# rev_B.net
KiCad netlist of a schematic drawn in EAGLE
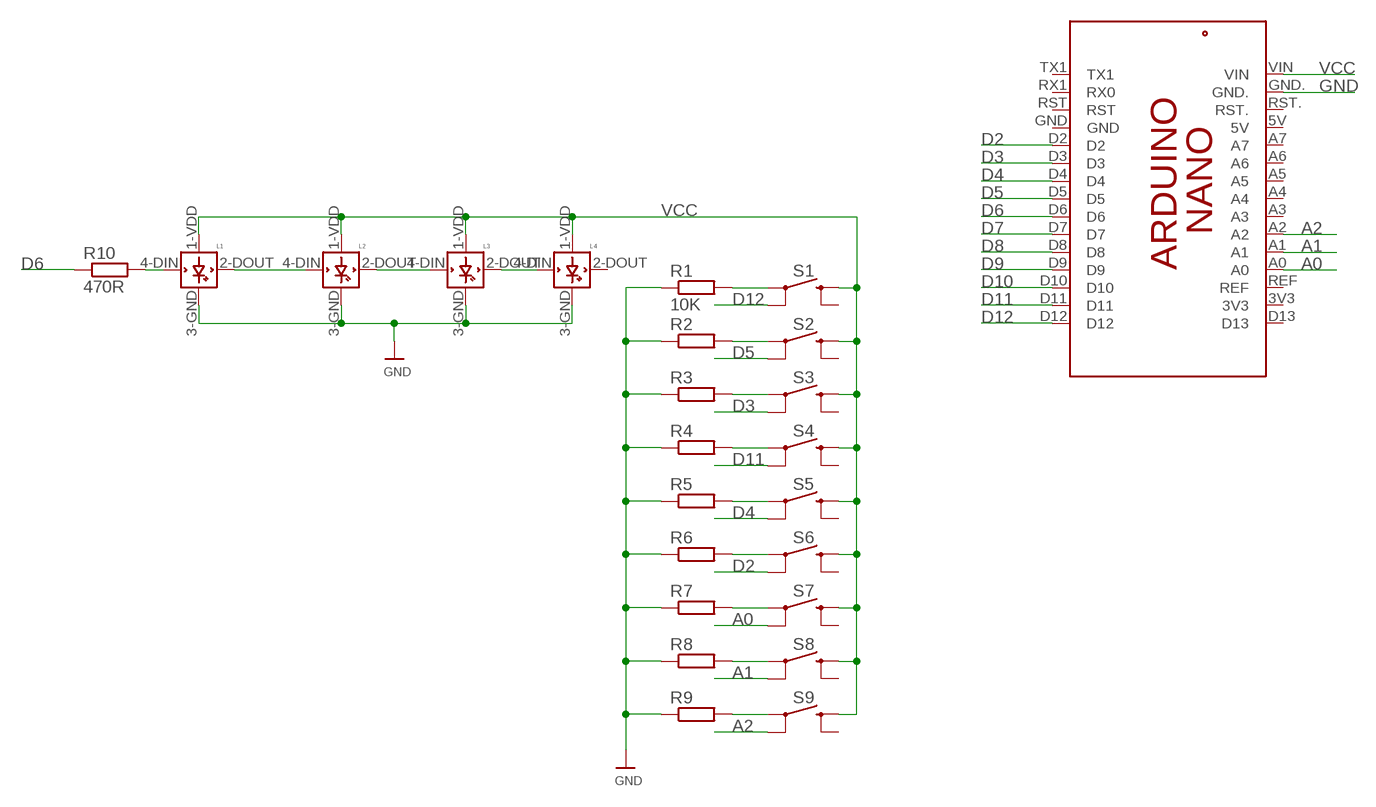
[diagram p0: schematic, sheet 1]

(export (version "E")
  (design (tool "Eeschema 10.0.6"))
  (components
    (comp (ref "L1")
      (value "WS2812B")
      (footprint "eagle-import:WS2812B")
      (libsource (lib "eagle-import") (part "WS2812B"))
    )
    (comp (ref "L2")
      (value "WS2812B")
      (footprint "eagle-import:WS2812B")
      (libsource (lib "eagle-import") (part "WS2812B"))
    )
    (comp (ref "L3")
      (value "WS2812B")
      (footprint "eagle-import:WS2812B")
      (libsource (lib "eagle-import") (part "WS2812B"))
    )
    (comp (ref "L4")
      (value "WS2812B")
      (footprint "eagle-import:WS2812B")
      (libsource (lib "eagle-import") (part "WS2812B"))
    )
    (comp (ref "PCB1")
      (value "ARDUINO_NANO")
      (footprint "eagle-import:ARDUINO_NANO")
      (libsource (lib "eagle-import") (part "ARDUINO_NANO"))
    )
    (comp (ref "R1")
      (value "10K")
      (footprint "eagle-import:R0805")
      (libsource (lib "eagle-import") (part "R-EU_R0805"))
    )
    (comp (ref "R2")
      (value "R-EU_R0805")
      (footprint "eagle-import:R0805")
      (libsource (lib "eagle-import") (part "R-EU_R0805"))
    )
    (comp (ref "R3")
      (value "R-EU_R0805")
      (footprint "eagle-import:R0805")
      (libsource (lib "eagle-import") (part "R-EU_R0805"))
    )
    (comp (ref "R4")
      (value "R-EU_R0805")
      (footprint "eagle-import:R0805")
      (libsource (lib "eagle-import") (part "R-EU_R0805"))
    )
    (comp (ref "R5")
      (value "R-EU_R0805")
      (footprint "eagle-import:R0805")
      (libsource (lib "eagle-import") (part "R-EU_R0805"))
    )
    (comp (ref "R6")
      (value "R-EU_R0805")
      (footprint "eagle-import:R0805")
      (libsource (lib "eagle-import") (part "R-EU_R0805"))
    )
    (comp (ref "R7")
      (value "R-EU_R0805")
      (footprint "eagle-import:R0805")
      (libsource (lib "eagle-import") (part "R-EU_R0805"))
    )
    (comp (ref "R8")
      (value "R-EU_R0805")
      (footprint "eagle-import:R0805")
      (libsource (lib "eagle-import") (part "R-EU_R0805"))
    )
    (comp (ref "R9")
      (value "R-EU_R0805")
      (footprint "eagle-import:R0805")
      (libsource (lib "eagle-import") (part "R-EU_R0805"))
    )
    (comp (ref "R10")
      (value "470R")
      (footprint "eagle-import:R0805")
      (libsource (lib "eagle-import") (part "R-EU_R0805"))
    )
    (comp (ref "S1")
      (value "TACT_SWITCH_12MM")
      (footprint "eagle-import:TACT_SWITCH_12MM")
      (libsource (lib "eagle-import") (part "TACT_SWITCH_12MM"))
    )
    (comp (ref "S2")
      (value "TACT_SWITCH_12MM")
      (footprint "eagle-import:TACT_SWITCH_12MM")
      (libsource (lib "eagle-import") (part "TACT_SWITCH_12MM"))
    )
    (comp (ref "S3")
      (value "TACT_SWITCH_12MM")
      (footprint "eagle-import:TACT_SWITCH_12MM")
      (libsource (lib "eagle-import") (part "TACT_SWITCH_12MM"))
    )
    (comp (ref "S4")
      (value "TACT_SWITCH_12MM")
      (footprint "eagle-import:TACT_SWITCH_12MM")
      (libsource (lib "eagle-import") (part "TACT_SWITCH_12MM"))
    )
    (comp (ref "S5")
      (value "TACT_SWITCH_12MM")
      (footprint "eagle-import:TACT_SWITCH_12MM")
      (libsource (lib "eagle-import") (part "TACT_SWITCH_12MM"))
    )
    (comp (ref "S6")
      (value "TACT_SWITCH_12MM")
      (footprint "eagle-import:TACT_SWITCH_12MM")
      (libsource (lib "eagle-import") (part "TACT_SWITCH_12MM"))
    )
    (comp (ref "S7")
      (value "TACT_SWITCH_12MM")
      (footprint "eagle-import:TACT_SWITCH_12MM")
      (libsource (lib "eagle-import") (part "TACT_SWITCH_12MM"))
    )
    (comp (ref "S8")
      (value "TACT_SWITCH_12MM")
      (footprint "eagle-import:TACT_SWITCH_12MM")
      (libsource (lib "eagle-import") (part "TACT_SWITCH_12MM"))
    )
    (comp (ref "S9")
      (value "TACT_SWITCH_12MM")
      (footprint "eagle-import:TACT_SWITCH_12MM")
      (libsource (lib "eagle-import") (part "TACT_SWITCH_12MM"))
    )
  )
  (nets
    (net (code "1") (name "/A0") (class "Default")
      (node (ref "PCB1") (pin "A0") (pinfunction "A0_A0") (pintype "bidirectional"))
      (node (ref "S7") (pin "2") (pinfunction "3_2") (pintype "passive"))
    )
    (net (code "2") (name "/A1") (class "Default")
      (node (ref "PCB1") (pin "A1") (pinfunction "A1_A1") (pintype "bidirectional"))
      (node (ref "S8") (pin "2") (pinfunction "3_2") (pintype "passive"))
    )
    (net (code "3") (name "/A2") (class "Default")
      (node (ref "PCB1") (pin "A2") (pinfunction "A2_A2") (pintype "bidirectional"))
      (node (ref "S9") (pin "2") (pinfunction "3_2") (pintype "passive"))
    )
    (net (code "4") (name "/D2") (class "Default")
      (node (ref "PCB1") (pin "D2") (pinfunction "D2_D2") (pintype "bidirectional"))
      (node (ref "S6") (pin "2") (pinfunction "3_2") (pintype "passive"))
    )
    (net (code "5") (name "/D3") (class "Default")
      (node (ref "PCB1") (pin "D3") (pinfunction "D3_D3") (pintype "bidirectional"))
      (node (ref "S3") (pin "2") (pinfunction "3_2") (pintype "passive"))
    )
    (net (code "6") (name "/D4") (class "Default")
      (node (ref "PCB1") (pin "D4") (pinfunction "D4_D4") (pintype "bidirectional"))
      (node (ref "S5") (pin "2") (pinfunction "3_2") (pintype "passive"))
    )
    (net (code "7") (name "/D5") (class "Default")
      (node (ref "PCB1") (pin "D5") (pinfunction "D5_D5") (pintype "bidirectional"))
      (node (ref "S2") (pin "2") (pinfunction "3_2") (pintype "passive"))
    )
    (net (code "8") (name "/D6") (class "Default")
      (node (ref "PCB1") (pin "D6") (pinfunction "D6_D6") (pintype "bidirectional"))
      (node (ref "R10") (pin "1") (pinfunction "1_1") (pintype "passive"))
    )
    (net (code "9") (name "/D7") (class "Default")
      (node (ref "PCB1") (pin "D7") (pinfunction "D7_D7") (pintype "bidirectional"))
    )
    (net (code "10") (name "/D8") (class "Default")
      (node (ref "PCB1") (pin "D8") (pinfunction "D8_D8") (pintype "bidirectional"))
    )
    (net (code "11") (name "/D9") (class "Default")
      (node (ref "PCB1") (pin "D9") (pinfunction "D9_D9") (pintype "bidirectional"))
    )
    (net (code "12") (name "/D10") (class "Default")
      (node (ref "PCB1") (pin "D10") (pinfunction "D10_D10") (pintype "bidirectional"))
    )
    (net (code "13") (name "/D11") (class "Default")
      (node (ref "PCB1") (pin "D11") (pinfunction "D11_D11") (pintype "bidirectional"))
      (node (ref "S4") (pin "2") (pinfunction "3_2") (pintype "passive"))
    )
    (net (code "14") (name "/D12") (class "Default")
      (node (ref "PCB1") (pin "D12") (pinfunction "D12_D12") (pintype "bidirectional"))
      (node (ref "S1") (pin "2") (pinfunction "3_2") (pintype "passive"))
    )
    (net (code "15") (name "/VCC") (class "Default")
      (node (ref "L1") (pin "1-VDD") (pinfunction "VDD_1-VDD") (pintype "bidirectional"))
      (node (ref "L2") (pin "1-VDD") (pinfunction "VDD_1-VDD") (pintype "bidirectional"))
      (node (ref "L3") (pin "1-VDD") (pinfunction "VDD_1-VDD") (pintype "bidirectional"))
      (node (ref "L4") (pin "1-VDD") (pinfunction "VDD_1-VDD") (pintype "bidirectional"))
      (node (ref "PCB1") (pin "VIN") (pinfunction "VIN_VIN") (pintype "bidirectional"))
      (node (ref "S1") (pin "3") (pinfunction "2_3") (pintype "passive"))
      (node (ref "S2") (pin "3") (pinfunction "2_3") (pintype "passive"))
      (node (ref "S3") (pin "3") (pinfunction "2_3") (pintype "passive"))
      (node (ref "S4") (pin "3") (pinfunction "2_3") (pintype "passive"))
      (node (ref "S5") (pin "3") (pinfunction "2_3") (pintype "passive"))
      (node (ref "S6") (pin "3") (pinfunction "2_3") (pintype "passive"))
      (node (ref "S7") (pin "3") (pinfunction "2_3") (pintype "passive"))
      (node (ref "S8") (pin "3") (pinfunction "2_3") (pintype "passive"))
      (node (ref "S9") (pin "3") (pinfunction "2_3") (pintype "passive"))
    )
    (net (code "16") (name "GND") (class "Default")
      (node (ref "L1") (pin "3-GND") (pinfunction "GND_3-GND") (pintype "bidirectional"))
      (node (ref "L2") (pin "3-GND") (pinfunction "GND_3-GND") (pintype "bidirectional"))
      (node (ref "L3") (pin "3-GND") (pinfunction "GND_3-GND") (pintype "bidirectional"))
      (node (ref "L4") (pin "3-GND") (pinfunction "GND_3-GND") (pintype "bidirectional"))
      (node (ref "PCB1") (pin "GND.") (pinfunction "GND._GND.") (pintype "bidirectional"))
      (node (ref "R1") (pin "1") (pinfunction "1_1") (pintype "passive"))
      (node (ref "R2") (pin "1") (pinfunction "1_1") (pintype "passive"))
      (node (ref "R3") (pin "1") (pinfunction "1_1") (pintype "passive"))
      (node (ref "R4") (pin "1") (pinfunction "1_1") (pintype "passive"))
      (node (ref "R5") (pin "1") (pinfunction "1_1") (pintype "passive"))
      (node (ref "R6") (pin "1") (pinfunction "1_1") (pintype "passive"))
      (node (ref "R7") (pin "1") (pinfunction "1_1") (pintype "passive"))
      (node (ref "R8") (pin "1") (pinfunction "1_1") (pintype "passive"))
      (node (ref "R9") (pin "1") (pinfunction "1_1") (pintype "passive"))
    )
    (net (code "17") (name "Net-(L1-DIN)") (class "Default")
      (node (ref "L1") (pin "4-DIN") (pinfunction "DIN_4-DIN") (pintype "input"))
      (node (ref "R10") (pin "2") (pinfunction "2_2") (pintype "passive"))
    )
    (net (code "18") (name "Net-(L1-DOUT)") (class "Default")
      (node (ref "L1") (pin "2-DOUT") (pinfunction "DOUT_2-DOUT") (pintype "output"))
      (node (ref "L2") (pin "4-DIN") (pinfunction "DIN_4-DIN") (pintype "input"))
    )
    (net (code "19") (name "Net-(L2-DOUT)") (class "Default")
      (node (ref "L2") (pin "2-DOUT") (pinfunction "DOUT_2-DOUT") (pintype "output"))
      (node (ref "L3") (pin "4-DIN") (pinfunction "DIN_4-DIN") (pintype "input"))
    )
    (net (code "20") (name "Net-(L3-DOUT)") (class "Default")
      (node (ref "L3") (pin "2-DOUT") (pinfunction "DOUT_2-DOUT") (pintype "output"))
      (node (ref "L4") (pin "4-DIN") (pinfunction "DIN_4-DIN") (pintype "input"))
    )
    (net (code "21") (name "Net-(R1-Pad2)") (class "Default")
      (node (ref "R1") (pin "2") (pinfunction "2_2") (pintype "passive"))
      (node (ref "S1") (pin "1") (pinfunction "1_1") (pintype "passive"))
    )
    (net (code "22") (name "Net-(R2-Pad2)") (class "Default")
      (node (ref "R2") (pin "2") (pinfunction "2_2") (pintype "passive"))
      (node (ref "S2") (pin "1") (pinfunction "1_1") (pintype "passive"))
    )
    (net (code "23") (name "Net-(R3-Pad2)") (class "Default")
      (node (ref "R3") (pin "2") (pinfunction "2_2") (pintype "passive"))
      (node (ref "S3") (pin "1") (pinfunction "1_1") (pintype "passive"))
    )
    (net (code "24") (name "Net-(R4-Pad2)") (class "Default")
      (node (ref "R4") (pin "2") (pinfunction "2_2") (pintype "passive"))
      (node (ref "S4") (pin "1") (pinfunction "1_1") (pintype "passive"))
    )
    (net (code "25") (name "Net-(R5-Pad2)") (class "Default")
      (node (ref "R5") (pin "2") (pinfunction "2_2") (pintype "passive"))
      (node (ref "S5") (pin "1") (pinfunction "1_1") (pintype "passive"))
    )
    (net (code "26") (name "Net-(R6-Pad2)") (class "Default")
      (node (ref "R6") (pin "2") (pinfunction "2_2") (pintype "passive"))
      (node (ref "S6") (pin "1") (pinfunction "1_1") (pintype "passive"))
    )
    (net (code "27") (name "Net-(R7-Pad2)") (class "Default")
      (node (ref "R7") (pin "2") (pinfunction "2_2") (pintype "passive"))
      (node (ref "S7") (pin "1") (pinfunction "1_1") (pintype "passive"))
    )
    (net (code "28") (name "Net-(R8-Pad2)") (class "Default")
      (node (ref "R8") (pin "2") (pinfunction "2_2") (pintype "passive"))
      (node (ref "S8") (pin "1") (pinfunction "1_1") (pintype "passive"))
    )
    (net (code "29") (name "Net-(R9-Pad2)") (class "Default")
      (node (ref "R9") (pin "2") (pinfunction "2_2") (pintype "passive"))
      (node (ref "S9") (pin "1") (pinfunction "1_1") (pintype "passive"))
    )
    (net (code "30") (name "unconnected-(L4-DOUT-Pad2-DOUT)") (class "Default")
      (node (ref "L4") (pin "2-DOUT") (pinfunction "DOUT_2-DOUT") (pintype "output"))
    )
    (net (code "31") (name "unconnected-(PCB1-Pad3V3)") (class "Default")
      (node (ref "PCB1") (pin "3V3") (pinfunction "3V3_3V3") (pintype "bidirectional"))
    )
    (net (code "32") (name "unconnected-(PCB1-Pad5V)") (class "Default")
      (node (ref "PCB1") (pin "5V") (pinfunction "5V_5V") (pintype "bidirectional"))
    )
    (net (code "33") (name "unconnected-(PCB1-PadA3)") (class "Default")
      (node (ref "PCB1") (pin "A3") (pinfunction "A3_A3") (pintype "bidirectional"))
    )
    (net (code "34") (name "unconnected-(PCB1-PadA4)") (class "Default")
      (node (ref "PCB1") (pin "A4") (pinfunction "A4_A4") (pintype "bidirectional"))
    )
    (net (code "35") (name "unconnected-(PCB1-PadA5)") (class "Default")
      (node (ref "PCB1") (pin "A5") (pinfunction "A5_A5") (pintype "bidirectional"))
    )
    (net (code "36") (name "unconnected-(PCB1-PadA6)") (class "Default")
      (node (ref "PCB1") (pin "A6") (pinfunction "A6_A6") (pintype "bidirectional"))
    )
    (net (code "37") (name "unconnected-(PCB1-PadA7)") (class "Default")
      (node (ref "PCB1") (pin "A7") (pinfunction "A7_A7") (pintype "bidirectional"))
    )
    (net (code "38") (name "unconnected-(PCB1-PadD13)") (class "Default")
      (node (ref "PCB1") (pin "D13") (pinfunction "D13_D13") (pintype "bidirectional"))
    )
    (net (code "39") (name "unconnected-(PCB1-PadGND)") (class "Default")
      (node (ref "PCB1") (pin "GND") (pinfunction "GND_GND") (pintype "bidirectional"))
    )
    (net (code "40") (name "unconnected-(PCB1-PadREF)") (class "Default")
      (node (ref "PCB1") (pin "REF") (pinfunction "REF_REF") (pintype "bidirectional"))
    )
    (net (code "41") (name "unconnected-(PCB1-PadRST)") (class "Default")
      (node (ref "PCB1") (pin "RST") (pinfunction "RST_RST") (pintype "bidirectional"))
    )
    (net (code "42") (name "unconnected-(PCB1-PadRST.)") (class "Default")
      (node (ref "PCB1") (pin "RST.") (pinfunction "RST._RST.") (pintype "bidirectional"))
    )
    (net (code "43") (name "unconnected-(PCB1-PadTX1)") (class "Default")
      (node (ref "PCB1") (pin "TX1") (pinfunction "TX1_TX1") (pintype "bidirectional"))
    )
    (net (code "44") (name "unconnected-(PCB1-RX0-PadRX1)") (class "Default")
      (node (ref "PCB1") (pin "RX1") (pinfunction "RX0_RX1") (pintype "bidirectional"))
    )
    (net (code "45") (name "unconnected-(S1-Pad4)") (class "Default")
      (node (ref "S1") (pin "4") (pinfunction "4_4") (pintype "passive"))
    )
    (net (code "46") (name "unconnected-(S2-Pad4)") (class "Default")
      (node (ref "S2") (pin "4") (pinfunction "4_4") (pintype "passive"))
    )
    (net (code "47") (name "unconnected-(S3-Pad4)") (class "Default")
      (node (ref "S3") (pin "4") (pinfunction "4_4") (pintype "passive"))
    )
    (net (code "48") (name "unconnected-(S4-Pad4)") (class "Default")
      (node (ref "S4") (pin "4") (pinfunction "4_4") (pintype "passive"))
    )
    (net (code "49") (name "unconnected-(S5-Pad4)") (class "Default")
      (node (ref "S5") (pin "4") (pinfunction "4_4") (pintype "passive"))
    )
    (net (code "50") (name "unconnected-(S6-Pad4)") (class "Default")
      (node (ref "S6") (pin "4") (pinfunction "4_4") (pintype "passive"))
    )
    (net (code "51") (name "unconnected-(S7-Pad4)") (class "Default")
      (node (ref "S7") (pin "4") (pinfunction "4_4") (pintype "passive"))
    )
    (net (code "52") (name "unconnected-(S8-Pad4)") (class "Default")
      (node (ref "S8") (pin "4") (pinfunction "4_4") (pintype "passive"))
    )
    (net (code "53") (name "unconnected-(S9-Pad4)") (class "Default")
      (node (ref "S9") (pin "4") (pinfunction "4_4") (pintype "passive"))
    )
  )
)
